# 24vStabilivolt_2025-04-15.net
KiCad netlist of a schematic drawn in EasyEDA Pro
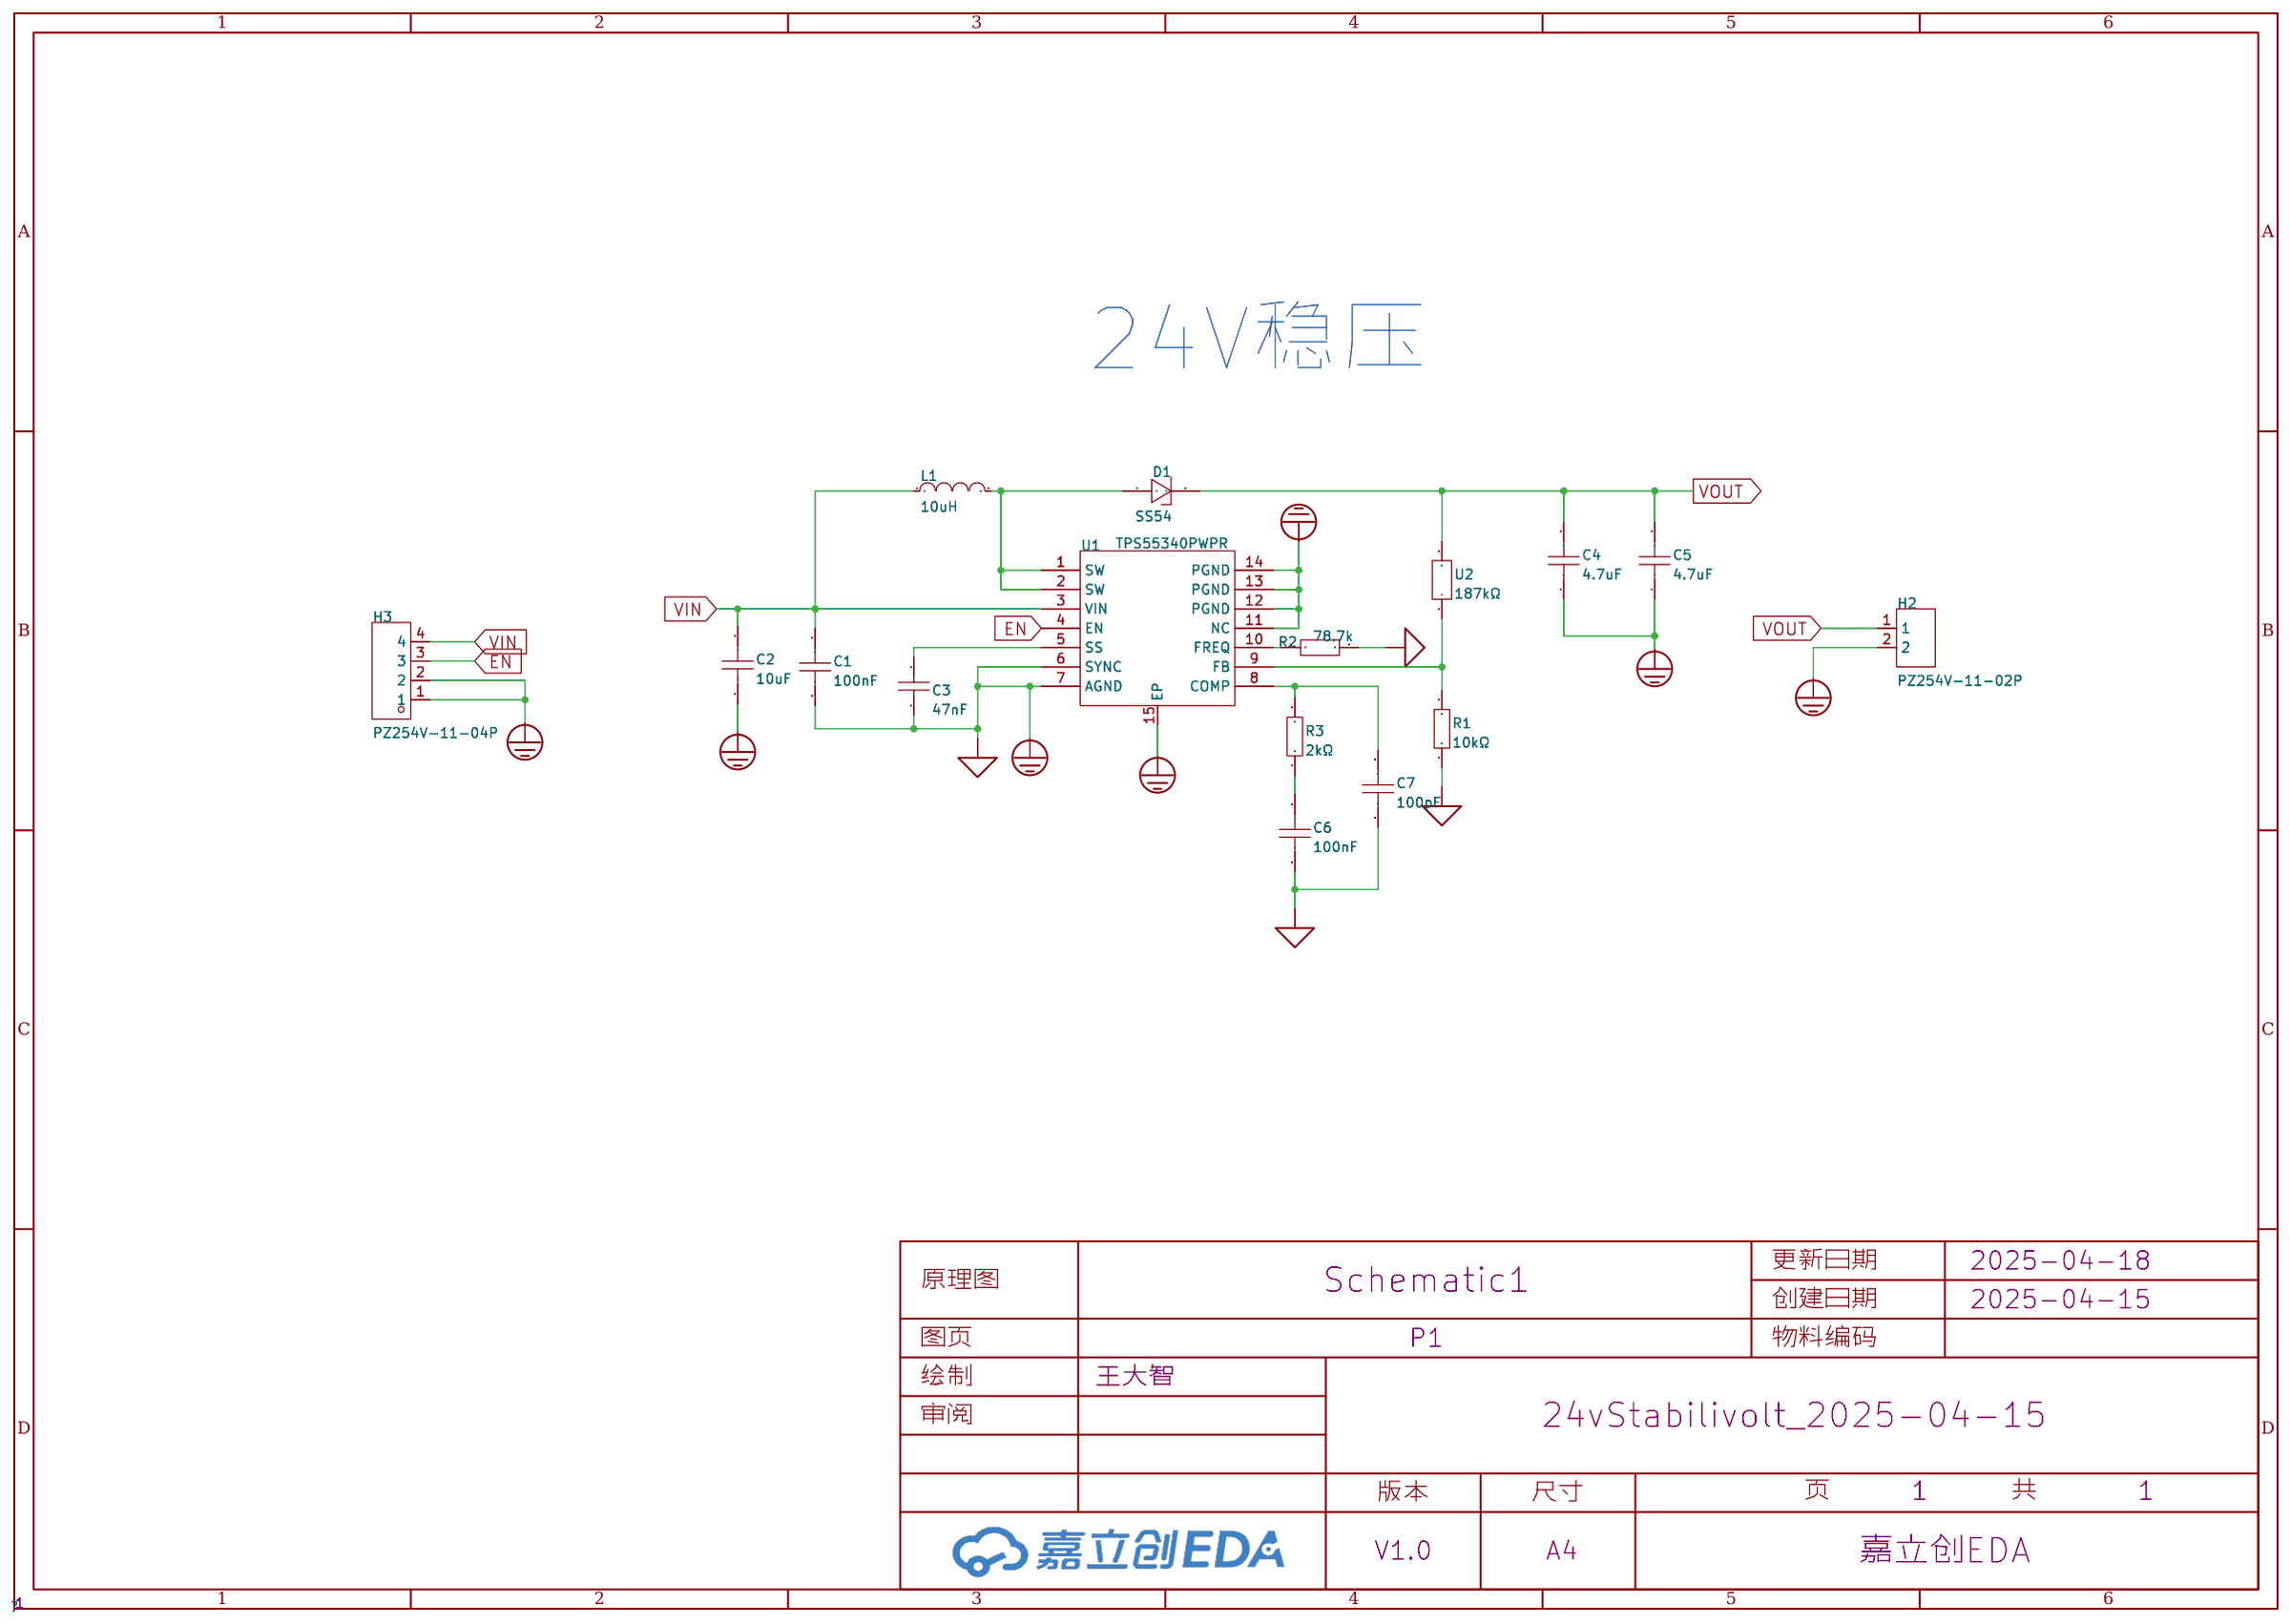
[diagram p0: schematic sheet]

(export (version "E")
  (design (tool "Eeschema 10.0.6"))
  (components
    (comp (ref "C1")
      (value "100nF")
      (footprint "easyedapro:C0603")
      (libsource (lib "easyedapro") (part "CapAcitance"))
    )
    (comp (ref "C2")
      (value "10uF")
      (footprint "easyedapro:C0805")
      (description "容值:10uF;精度:±10%;额定电压:35V;温度系数:X5R;")
      (fields
        (field (name "Manufacturer Part") "CGA0805X5R106K350MT")
        (field (name "Manufacturer") "HRE(芯声)")
      )
      (libsource (lib "easyedapro") (part "CGA0805X5R106K350MT"))
    )
    (comp (ref "C3")
      (value "47nF")
      (footprint "easyedapro:C0603")
      (description "容值:47nF;精度:±10%;额定电压:50V;材质(温度系数):X7R;")
      (fields
        (field (name "Manufacturer Part") "CL10B473KB8NNNC")
        (field (name "Manufacturer") "SAMSUNG(三星)")
      )
      (libsource (lib "easyedapro") (part "CL10B473KB8NNNC"))
    )
    (comp (ref "C4")
      (value "4.7uF")
      (footprint "easyedapro:C0805")
      (description "容值:4.7uF;精度:±10%;额定电压:35V;材质(温度系数):X7R;")
      (fields
        (field (name "Manufacturer Part") "CGA0805X7R475K350MT")
        (field (name "Manufacturer") "HRE(芯声)")
      )
      (libsource (lib "easyedapro") (part "CGA0805X7R475K350MT"))
    )
    (comp (ref "C5")
      (value "4.7uF")
      (footprint "easyedapro:C0805")
      (description "容值:4.7uF;精度:±10%;额定电压:35V;材质(温度系数):X7R;")
      (fields
        (field (name "Manufacturer Part") "CGA0805X7R475K350MT")
        (field (name "Manufacturer") "HRE(芯声)")
      )
      (libsource (lib "easyedapro") (part "CGA0805X7R475K350MT"))
    )
    (comp (ref "C6")
      (value "100nF")
      (footprint "easyedapro:C0603")
      (description "容值:100nF;精度:±10%;额定电压:50V;温度系数:X7R;")
      (fields
        (field (name "Manufacturer Part") "CGA0603X7R104K500JT")
        (field (name "Manufacturer") "HRE(芯声)")
      )
      (libsource (lib "easyedapro") (part "CGA0603X7R104K500JT"))
    )
    (comp (ref "C7")
      (value "100pF")
      (footprint "easyedapro:C0603")
      (description "容值:100pF;精度:±5%;额定电压:50V;材质(温度系数):NP0;")
      (fields
        (field (name "Manufacturer Part") "CC0603JRNPO9BN101")
        (field (name "Manufacturer") "YAGEO(国巨)")
      )
      (libsource (lib "easyedapro") (part "CC0603JRNPO9BN101"))
    )
    (comp (ref "D1")
      (value "SS54")
      (footprint "easyedapro:SMA_L4.3-W2.6-LS5.0-FD")
      (description "二极管配置:独立式;正向压降(Vf):550mV@5.0A;直流反向耐压(Vr):40V;整流电流:5A;")
      (fields (field (name "Manufacturer") "宏迦橙"))
      (libsource (lib "easyedapro") (part "SS54_C7420369"))
    )
    (comp (ref "H2")
      (value "PZ254V-11-02P")
      (footprint "easyedapro:HDR-TH_2P-P2.54-V-M")
      (fields (field (name "Manufacturer") "XFCN(兴飞)"))
      (libsource (lib "easyedapro") (part "PZ254V-11-02P"))
    )
    (comp (ref "H3")
      (value "PZ254V-11-04P")
      (footprint "easyedapro:HDR-TH_4P-P2.54-V-M")
      (fields (field (name "Manufacturer") "XFCN(兴飞)"))
      (libsource (lib "easyedapro") (part "PZ254V-11-04P_C2691448"))
    )
    (comp (ref "L1")
      (value "10uH")
      (footprint "easyedapro:IND-SMD_L7.3-W6.8")
      (description "电感值:10uH;精度:±20%;额定电流:4.5A;饱和电流(Isat):5.5A;类型:一体成型电感;")
      (fields (field (name "Manufacturer Part") "FXL0630-100-M") (field (name "Manufacturer") "cjiang(长江微电)"))
      (libsource (lib "easyedapro") (part "FXL0630-100-M"))
    )
    (comp (ref "R1")
      (value "10kΩ")
      (footprint "easyedapro:R0603")
      (description "电阻类型:厚膜电阻;阻值:10kΩ;精度:±1%;功率:100mW;最大工作电压:75V;温度系数:±100ppm/°C;")
      (fields (field (name "Manufacturer Part") "RC0603FR-0710KL") (field (name "Manufacturer") "YAGEO(国巨)"))
      (libsource (lib "easyedapro") (part "RC0603FR-0710KL"))
    )
    (comp (ref "R2")
      (value "78.7k")
      (footprint "easyedapro:R0603")
      (libsource (lib "easyedapro") (part "电阻"))
    )
    (comp (ref "R3")
      (value "2kΩ")
      (footprint "easyedapro:R0603")
      (description "电阻类型:厚膜电阻;阻值:2kΩ;精度:±1%;功率:100mW;最大工作电压:75V;温度系数:±100ppm/°C;")
      (fields
        (field (name "Manufacturer Part") "0603WAF2001T5E")
        (field (name "Manufacturer") "UNI-ROYAL(厚声)")
      )
      (libsource (lib "easyedapro") (part "0603WAF2001T5E"))
    )
    (comp (ref "U1")
      (value "TPS55340PWPR")
      (footprint "easyedapro:HTSSOP-14_L5.0-W4.4-P0.65-LS6.4-BL-EP")
      (description "功能类型:升压型;输出类型:固定;工作电压:2.9V~32V;输出电压:24V;输出电流:5.25A;")
      (fields (field (name "Manufacturer") "TI(德州仪器)"))
      (libsource (lib "easyedapro") (part "TPS55340PWPR"))
    )
    (comp (ref "U2")
      (value "187kΩ")
      (footprint "easyedapro:R0603")
      (description "电阻类型:厚膜电阻;阻值:187kΩ;精度:±1%;功率:100mW;最大工作电压:75V;温度系数:±100ppm/°C;")
      (fields (field (name "Manufacturer Part") "FRC0603F1873TS") (field (name "Manufacturer") "FOJAN(富捷)"))
      (libsource (lib "easyedapro") (part "FRC0603F1873TS"))
    )
  )
  (nets
    (net (code "1") (name "AGND") (class "Default")
      (node (ref "C6") (pin "1") (pinfunction "1_1") (pintype "unspecified"))
      (node (ref "C7") (pin "1") (pinfunction "1_1") (pintype "unspecified"))
      (node (ref "R1") (pin "1") (pinfunction "1_1") (pintype "input"))
      (node (ref "R2") (pin "2") (pinfunction "2_2") (pintype "input"))
    )
    (net (code "2") (name "EN") (class "Default")
      (node (ref "H3") (pin "3") (pinfunction "3_3") (pintype "unspecified"))
      (node (ref "U1") (pin "4") (pinfunction "EN_4") (pintype "unspecified"))
    )
    (net (code "3") (name "Net-(C6-Pad2)") (class "Default")
      (node (ref "C6") (pin "2") (pinfunction "2_2") (pintype "unspecified"))
      (node (ref "R3") (pin "1") (pinfunction "1_1") (pintype "input"))
    )
    (net (code "4") (name "Net-(D1-A)") (class "Default")
      (node (ref "D1") (pin "1") (pinfunction "A_1") (pintype "unspecified"))
      (node (ref "L1") (pin "2") (pinfunction "2_2") (pintype "unspecified"))
      (node (ref "U1") (pin "1") (pinfunction "SW_1") (pintype "unspecified"))
      (node (ref "U1") (pin "2") (pinfunction "SW_2") (pintype "unspecified"))
    )
    (net (code "5") (name "Net-(U1-COMP)") (class "Default")
      (node (ref "C7") (pin "2") (pinfunction "2_2") (pintype "unspecified"))
      (node (ref "R3") (pin "2") (pinfunction "2_2") (pintype "input"))
      (node (ref "U1") (pin "8") (pinfunction "COMP_8") (pintype "unspecified"))
    )
    (net (code "6") (name "Net-(U1-FB)") (class "Default")
      (node (ref "R1") (pin "2") (pinfunction "2_2") (pintype "input"))
      (node (ref "U1") (pin "9") (pinfunction "FB_9") (pintype "unspecified"))
      (node (ref "U2") (pin "1") (pinfunction "1_1") (pintype "unspecified"))
    )
    (net (code "7") (name "Net-(U1-FREQ)") (class "Default")
      (node (ref "R2") (pin "1") (pinfunction "1_1") (pintype "input"))
      (node (ref "U1") (pin "10") (pinfunction "FREQ_10") (pintype "unspecified"))
    )
    (net (code "8") (name "Net-(U1-SS)") (class "Default")
      (node (ref "C3") (pin "2") (pinfunction "2_2") (pintype "input"))
      (node (ref "U1") (pin "5") (pinfunction "SS_5") (pintype "unspecified"))
    )
    (net (code "9") (name "PGND") (class "Default")
      (node (ref "C1") (pin "1") (pinfunction "1_1") (pintype "input"))
      (node (ref "C2") (pin "1") (pinfunction "1_1") (pintype "unspecified"))
      (node (ref "C3") (pin "1") (pinfunction "1_1") (pintype "input"))
      (node (ref "C4") (pin "1") (pinfunction "1_1") (pintype "unspecified"))
      (node (ref "C5") (pin "1") (pinfunction "1_1") (pintype "unspecified"))
      (node (ref "H2") (pin "2") (pinfunction "2_2") (pintype "unspecified"))
      (node (ref "H3") (pin "1") (pinfunction "1_1") (pintype "unspecified"))
      (node (ref "H3") (pin "2") (pinfunction "2_2") (pintype "unspecified"))
      (node (ref "U1") (pin "11") (pinfunction "NC_11") (pintype "unspecified"))
      (node (ref "U1") (pin "12") (pinfunction "PGND_12") (pintype "unspecified"))
      (node (ref "U1") (pin "13") (pinfunction "PGND_13") (pintype "unspecified"))
      (node (ref "U1") (pin "14") (pinfunction "PGND_14") (pintype "unspecified"))
      (node (ref "U1") (pin "15") (pinfunction "EP_15") (pintype "unspecified"))
      (node (ref "U1") (pin "6") (pinfunction "SYNC_6") (pintype "unspecified"))
      (node (ref "U1") (pin "7") (pinfunction "AGND_7") (pintype "unspecified"))
    )
    (net (code "10") (name "VIN") (class "Default")
      (node (ref "C1") (pin "2") (pinfunction "2_2") (pintype "input"))
      (node (ref "C2") (pin "2") (pinfunction "2_2") (pintype "unspecified"))
      (node (ref "H3") (pin "4") (pinfunction "4_4") (pintype "unspecified"))
      (node (ref "L1") (pin "1") (pinfunction "1_1") (pintype "unspecified"))
      (node (ref "U1") (pin "3") (pinfunction "VIN_3") (pintype "unspecified"))
    )
    (net (code "11") (name "VOUT") (class "Default")
      (node (ref "C4") (pin "2") (pinfunction "2_2") (pintype "unspecified"))
      (node (ref "C5") (pin "2") (pinfunction "2_2") (pintype "unspecified"))
      (node (ref "D1") (pin "2") (pinfunction "K_2") (pintype "unspecified"))
      (node (ref "H2") (pin "1") (pinfunction "1_1") (pintype "unspecified"))
      (node (ref "U2") (pin "2") (pinfunction "2_2") (pintype "unspecified"))
    )
  )
)
